# mos_board.net
KiCad netlist of a schematic drawn in Altium Designer
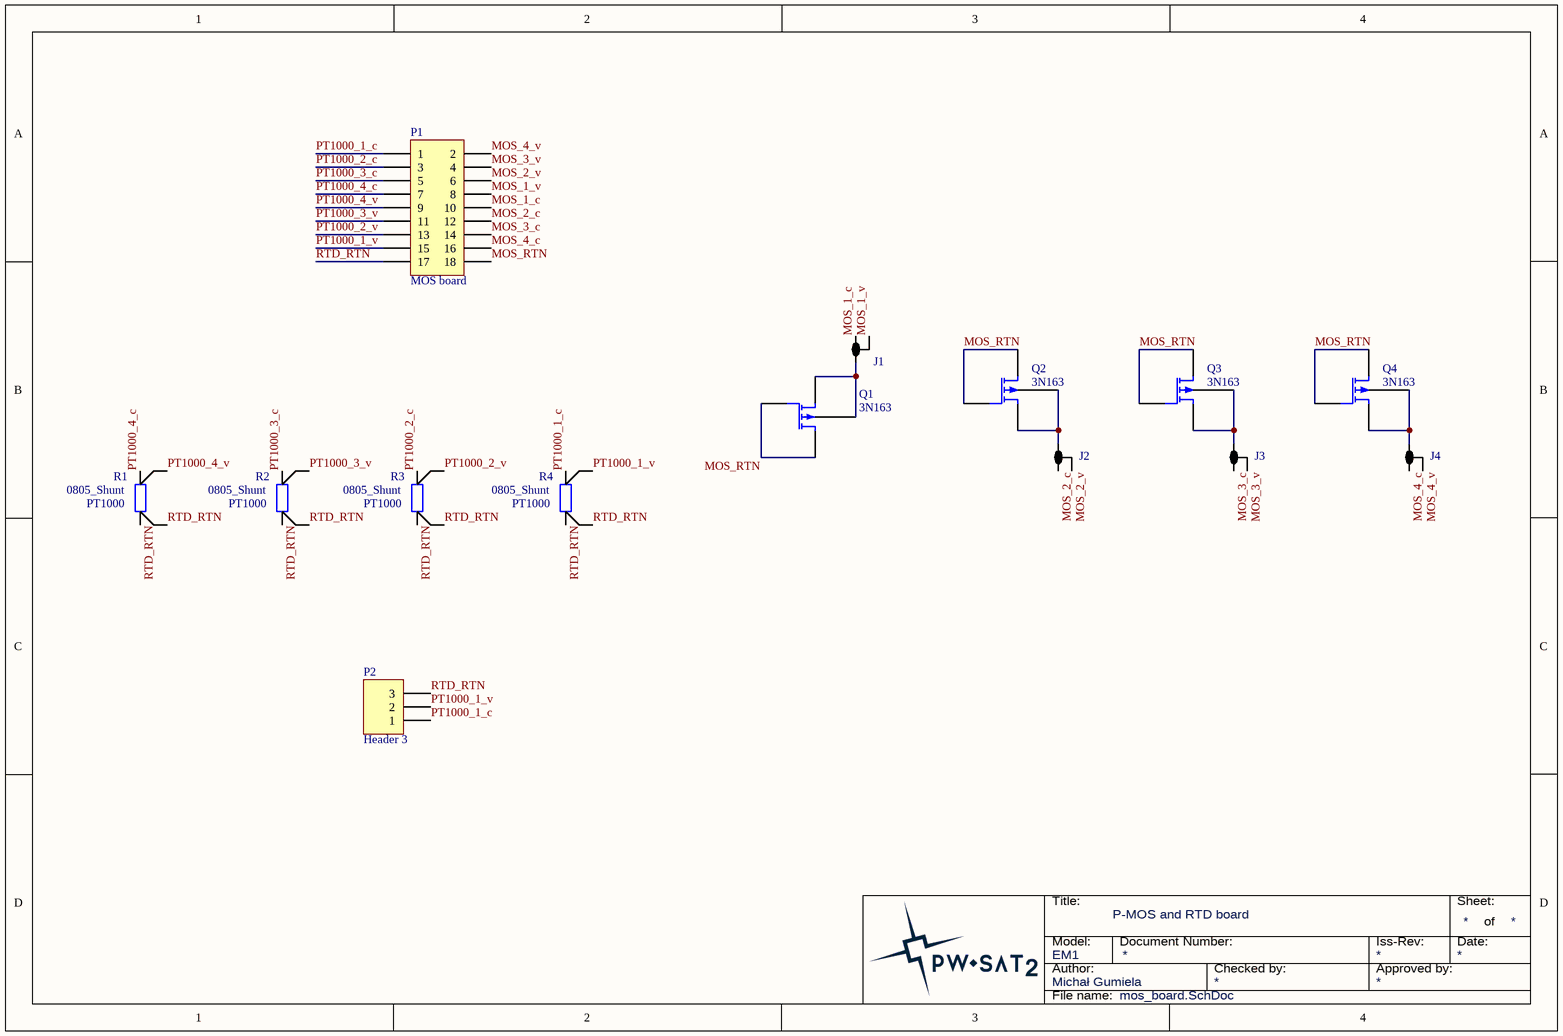
[diagram p0: mos_board.SchDoc]

(export (version "E")
  (design (tool "Eeschema 10.0.6"))
  (components
    (comp (ref "J1")
      (value "3 way net tie junction Y shape")
      (footprint "3wayY_LP")
      (libsource (lib "NetTieLib") (part "3wayY"))
    )
    (comp (ref "J2")
      (value "3 way net tie junction Y shape")
      (footprint "3wayY_LP")
      (libsource (lib "") (part "3wayY_1"))
    )
    (comp (ref "J3")
      (value "3 way net tie junction Y shape")
      (footprint "3wayY_LP")
      (libsource (lib "") (part "3wayY_1"))
    )
    (comp (ref "J4")
      (value "3 way net tie junction Y shape")
      (footprint "3wayY_LP")
      (libsource (lib "") (part "3wayY_1"))
    )
    (comp (ref "P1")
      (value "MOS board")
      (footprint "HDR2X9")
      (description "Header, 9-Pin, Dual row")
      (fields (field (name "PUBLISHER") "Altium Limited"))
      (libsource (lib "Miscellaneous Connectors") (part "Header 9X2"))
    )
    (comp (ref "P2")
      (value "Header 3")
      (footprint "HDR1X3")
      (description "Header, 3-Pin")
      (fields (field (name "PUBLISHER") "Altium Limited"))
      (libsource (lib "Miscellaneous Connectors") (part "Header 3"))
    )
    (comp (ref "Q1")
      (value "3N163")
      (footprint "TO-206AF")
      (description "P-MOS for military application")
      (libsource (lib "3N163") (part "3N163"))
    )
    (comp (ref "Q2")
      (value "3N163")
      (footprint "TO-206AF")
      (description "P-MOS for military application")
      (libsource (lib "3N163") (part "3N163"))
    )
    (comp (ref "Q3")
      (value "3N163")
      (footprint "TO-206AF")
      (description "P-MOS for military application")
      (libsource (lib "3N163") (part "3N163"))
    )
    (comp (ref "Q4")
      (value "3N163")
      (footprint "TO-206AF")
      (description "P-MOS for military application")
      (libsource (lib "3N163") (part "3N163"))
    )
    (comp (ref "R1")
      (value "PT1000")
      (footprint "SMD_Resistor-shunt_0805")
      (description "Platinum Thin-Film Chip Sensor")
      (fields
        (field (name "MANUFACTURER") "IST INNOVATIVE SENSOR TECHNOLOGY")
        (field (name "MANUFACTURERPARTNUMBER") "P1K0.0805.2P.A")
        (field (name "PACKAGE") "0805_Shunt")
      )
      (libsource (lib "resistors") (part "PT1000"))
    )
    (comp (ref "R2")
      (value "PT1000")
      (footprint "SMD_Resistor-shunt_0805")
      (description "Platinum Thin-Film Chip Sensor")
      (fields
        (field (name "MANUFACTURER") "IST INNOVATIVE SENSOR TECHNOLOGY")
        (field (name "MANUFACTURERPARTNUMBER") "P1K0.0805.2P.A")
        (field (name "PACKAGE") "0805_Shunt")
      )
      (libsource (lib "resistors") (part "PT1000"))
    )
    (comp (ref "R3")
      (value "PT1000")
      (footprint "SMD_Resistor-shunt_0805")
      (description "Platinum Thin-Film Chip Sensor")
      (fields
        (field (name "MANUFACTURER") "IST INNOVATIVE SENSOR TECHNOLOGY")
        (field (name "MANUFACTURERPARTNUMBER") "P1K0.0805.2P.A")
        (field (name "PACKAGE") "0805_Shunt")
      )
      (libsource (lib "resistors") (part "PT1000"))
    )
    (comp (ref "R4")
      (value "PT1000")
      (footprint "SMD_Resistor-shunt_0805")
      (description "Platinum Thin-Film Chip Sensor")
      (fields
        (field (name "MANUFACTURER") "IST INNOVATIVE SENSOR TECHNOLOGY")
        (field (name "MANUFACTURERPARTNUMBER") "P1K0.0805.2P.A")
        (field (name "PACKAGE") "0805_Shunt")
      )
      (libsource (lib "resistors") (part "PT1000"))
    )
  )
  (nets
    (net (code "1") (name "/MOS_1_c") (class "Default")
      (node (ref "J1") (pin "3") (pinfunction "3_3") (pintype "passive"))
      (node (ref "P1") (pin "10") (pinfunction "10_10") (pintype "passive"))
    )
    (net (code "2") (name "/MOS_1_v") (class "Default")
      (node (ref "J1") (pin "2") (pinfunction "2_2") (pintype "passive"))
      (node (ref "P1") (pin "8") (pinfunction "8_8") (pintype "passive"))
    )
    (net (code "3") (name "/MOS_2_c") (class "Default")
      (node (ref "J2") (pin "3") (pinfunction "3_3") (pintype "passive"))
      (node (ref "P1") (pin "12") (pinfunction "12_12") (pintype "passive"))
    )
    (net (code "4") (name "/MOS_2_v") (class "Default")
      (node (ref "J2") (pin "2") (pinfunction "2_2") (pintype "passive"))
      (node (ref "P1") (pin "6") (pinfunction "6_6") (pintype "passive"))
    )
    (net (code "5") (name "/MOS_3_c") (class "Default")
      (node (ref "J3") (pin "3") (pinfunction "3_3") (pintype "passive"))
      (node (ref "P1") (pin "14") (pinfunction "14_14") (pintype "passive"))
    )
    (net (code "6") (name "/MOS_3_v") (class "Default")
      (node (ref "J3") (pin "2") (pinfunction "2_2") (pintype "passive"))
      (node (ref "P1") (pin "4") (pinfunction "4_4") (pintype "passive"))
    )
    (net (code "7") (name "/MOS_4_c") (class "Default")
      (node (ref "J4") (pin "3") (pinfunction "3_3") (pintype "passive"))
      (node (ref "P1") (pin "16") (pinfunction "16_16") (pintype "passive"))
    )
    (net (code "8") (name "/MOS_4_v") (class "Default")
      (node (ref "J4") (pin "2") (pinfunction "2_2") (pintype "passive"))
      (node (ref "P1") (pin "2") (pinfunction "2_2") (pintype "passive"))
    )
    (net (code "9") (name "/MOS_RTN") (class "Default")
      (node (ref "P1") (pin "18") (pinfunction "18_18") (pintype "passive"))
      (node (ref "Q1") (pin "1") (pinfunction "D_1") (pintype "passive"))
      (node (ref "Q1") (pin "2") (pinfunction "G_2") (pintype "passive"))
      (node (ref "Q2") (pin "1") (pinfunction "D_1") (pintype "passive"))
      (node (ref "Q2") (pin "2") (pinfunction "G_2") (pintype "passive"))
      (node (ref "Q3") (pin "1") (pinfunction "D_1") (pintype "passive"))
      (node (ref "Q3") (pin "2") (pinfunction "G_2") (pintype "passive"))
      (node (ref "Q4") (pin "1") (pinfunction "D_1") (pintype "passive"))
      (node (ref "Q4") (pin "2") (pinfunction "G_2") (pintype "passive"))
    )
    (net (code "10") (name "/PT1000_1_c") (class "Default")
      (node (ref "P1") (pin "1") (pinfunction "1_1") (pintype "passive"))
      (node (ref "P2") (pin "1") (pinfunction "1_1") (pintype "passive"))
      (node (ref "R4") (pin "1") (pinfunction "1_1") (pintype "passive"))
    )
    (net (code "11") (name "/PT1000_1_v") (class "Default")
      (node (ref "P1") (pin "15") (pinfunction "15_15") (pintype "passive"))
      (node (ref "P2") (pin "2") (pinfunction "2_2") (pintype "passive"))
      (node (ref "R4") (pin "2") (pinfunction "2_2") (pintype "passive"))
    )
    (net (code "12") (name "/PT1000_2_c") (class "Default")
      (node (ref "P1") (pin "3") (pinfunction "3_3") (pintype "passive"))
      (node (ref "R3") (pin "1") (pinfunction "1_1") (pintype "passive"))
    )
    (net (code "13") (name "/PT1000_2_v") (class "Default")
      (node (ref "P1") (pin "13") (pinfunction "13_13") (pintype "passive"))
      (node (ref "R3") (pin "2") (pinfunction "2_2") (pintype "passive"))
    )
    (net (code "14") (name "/PT1000_3_c") (class "Default")
      (node (ref "P1") (pin "5") (pinfunction "5_5") (pintype "passive"))
      (node (ref "R2") (pin "1") (pinfunction "1_1") (pintype "passive"))
    )
    (net (code "15") (name "/PT1000_3_v") (class "Default")
      (node (ref "P1") (pin "11") (pinfunction "11_11") (pintype "passive"))
      (node (ref "R2") (pin "2") (pinfunction "2_2") (pintype "passive"))
    )
    (net (code "16") (name "/PT1000_4_c") (class "Default")
      (node (ref "P1") (pin "7") (pinfunction "7_7") (pintype "passive"))
      (node (ref "R1") (pin "1") (pinfunction "1_1") (pintype "passive"))
    )
    (net (code "17") (name "/PT1000_4_v") (class "Default")
      (node (ref "P1") (pin "9") (pinfunction "9_9") (pintype "passive"))
      (node (ref "R1") (pin "2") (pinfunction "2_2") (pintype "passive"))
    )
    (net (code "18") (name "/RTD_RTN") (class "Default")
      (node (ref "P1") (pin "17") (pinfunction "17_17") (pintype "passive"))
      (node (ref "P2") (pin "3") (pinfunction "3_3") (pintype "passive"))
      (node (ref "R1") (pin "3") (pinfunction "3_3") (pintype "passive"))
      (node (ref "R1") (pin "4") (pinfunction "4_4") (pintype "passive"))
      (node (ref "R2") (pin "3") (pinfunction "3_3") (pintype "passive"))
      (node (ref "R2") (pin "4") (pinfunction "4_4") (pintype "passive"))
      (node (ref "R3") (pin "3") (pinfunction "3_3") (pintype "passive"))
      (node (ref "R3") (pin "4") (pinfunction "4_4") (pintype "passive"))
      (node (ref "R4") (pin "3") (pinfunction "3_3") (pintype "passive"))
      (node (ref "R4") (pin "4") (pinfunction "4_4") (pintype "passive"))
    )
    (net (code "19") (name "Net-(Q1-B)") (class "Default")
      (node (ref "J1") (pin "1") (pinfunction "1_1") (pintype "passive"))
      (node (ref "Q1") (pin "3") (pinfunction "B_3") (pintype "passive"))
      (node (ref "Q1") (pin "4") (pinfunction "S_4") (pintype "passive"))
    )
    (net (code "20") (name "Net-(Q2-B)") (class "Default")
      (node (ref "J2") (pin "1") (pinfunction "1_1") (pintype "passive"))
      (node (ref "Q2") (pin "3") (pinfunction "B_3") (pintype "passive"))
      (node (ref "Q2") (pin "4") (pinfunction "S_4") (pintype "passive"))
    )
    (net (code "21") (name "Net-(Q3-B)") (class "Default")
      (node (ref "J3") (pin "1") (pinfunction "1_1") (pintype "passive"))
      (node (ref "Q3") (pin "3") (pinfunction "B_3") (pintype "passive"))
      (node (ref "Q3") (pin "4") (pinfunction "S_4") (pintype "passive"))
    )
    (net (code "22") (name "Net-(Q4-B)") (class "Default")
      (node (ref "J4") (pin "1") (pinfunction "1_1") (pintype "passive"))
      (node (ref "Q4") (pin "3") (pinfunction "B_3") (pintype "passive"))
      (node (ref "Q4") (pin "4") (pinfunction "S_4") (pintype "passive"))
    )
  )
)
